# PCB-BI8-2x4C3.net
KiCad netlist of a schematic drawn in EAGLE
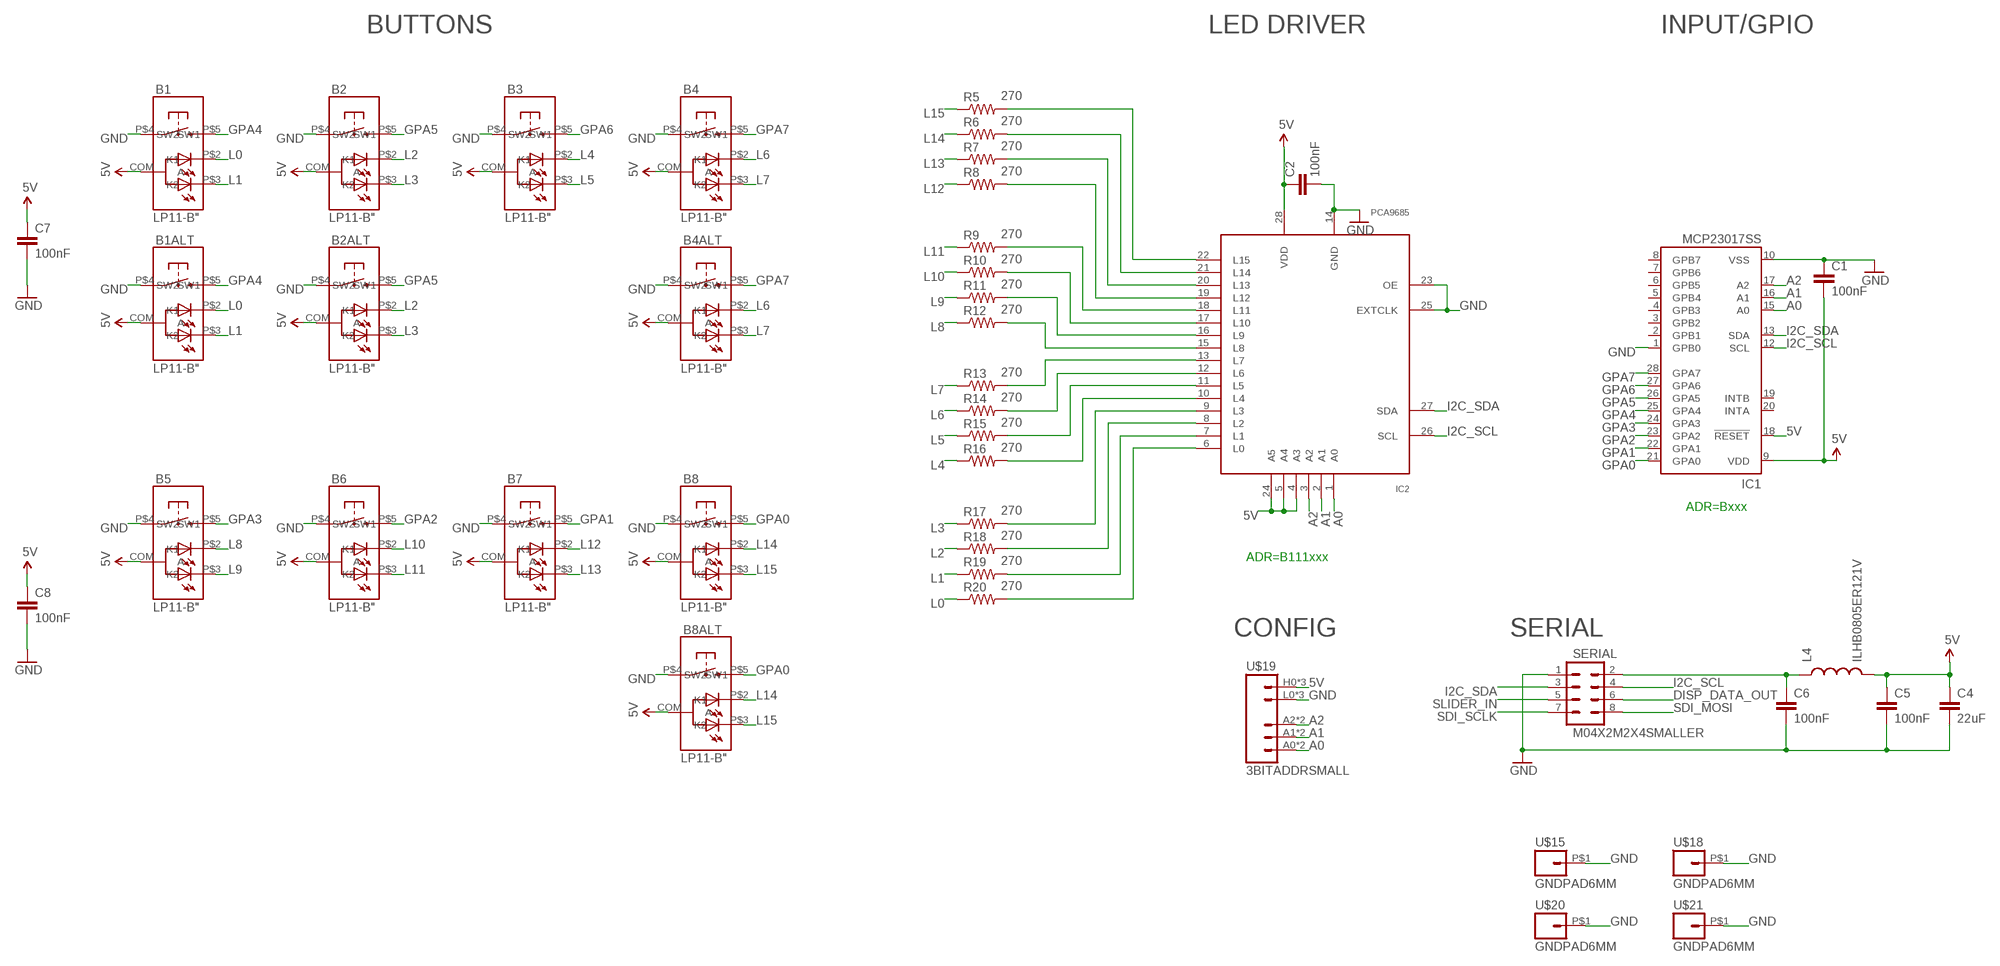
[diagram p0: schematic, sheet 1]

(export (version "E")
  (design (tool "Eeschema 10.0.6"))
  (components
    (comp (ref "B1")
      (value "LP11-B\"")
      (footprint "eagle-import:LP11")
      (libsource (lib "eagle-import") (part "LP11-B{dblquote}"))
    )
    (comp (ref "B1ALT")
      (value "LP11-B\"")
      (footprint "eagle-import:LP11")
      (libsource (lib "eagle-import") (part "LP11-B{dblquote}"))
    )
    (comp (ref "B2")
      (value "LP11-B\"")
      (footprint "eagle-import:LP11")
      (libsource (lib "eagle-import") (part "LP11-B{dblquote}"))
    )
    (comp (ref "B2ALT")
      (value "LP11-B\"")
      (footprint "eagle-import:LP11")
      (libsource (lib "eagle-import") (part "LP11-B{dblquote}"))
    )
    (comp (ref "B3")
      (value "LP11-B\"")
      (footprint "eagle-import:LP11")
      (libsource (lib "eagle-import") (part "LP11-B{dblquote}"))
    )
    (comp (ref "B4")
      (value "LP11-B\"")
      (footprint "eagle-import:LP11")
      (libsource (lib "eagle-import") (part "LP11-B{dblquote}"))
    )
    (comp (ref "B4ALT")
      (value "LP11-B\"")
      (footprint "eagle-import:LP11")
      (libsource (lib "eagle-import") (part "LP11-B{dblquote}"))
    )
    (comp (ref "B5")
      (value "LP11-B\"")
      (footprint "eagle-import:LP11")
      (libsource (lib "eagle-import") (part "LP11-B{dblquote}"))
    )
    (comp (ref "B6")
      (value "LP11-B\"")
      (footprint "eagle-import:LP11")
      (libsource (lib "eagle-import") (part "LP11-B{dblquote}"))
    )
    (comp (ref "B7")
      (value "LP11-B\"")
      (footprint "eagle-import:LP11")
      (libsource (lib "eagle-import") (part "LP11-B{dblquote}"))
    )
    (comp (ref "B8")
      (value "LP11-B\"")
      (footprint "eagle-import:LP11")
      (libsource (lib "eagle-import") (part "LP11-B{dblquote}"))
    )
    (comp (ref "B8ALT")
      (value "LP11-B\"")
      (footprint "eagle-import:LP11")
      (libsource (lib "eagle-import") (part "LP11-B{dblquote}"))
    )
    (comp (ref "C1")
      (value "100nF")
      (footprint "eagle-import:0603-CAP")
      (libsource (lib "eagle-import") (part "CAP0603-CAP"))
    )
    (comp (ref "C2")
      (value "100nF")
      (footprint "eagle-import:0603-CAP")
      (libsource (lib "eagle-import") (part "CAP0603-CAP"))
    )
    (comp (ref "C4")
      (value "22uF")
      (footprint "eagle-import:0805")
      (libsource (lib "eagle-import") (part "CAP0805"))
    )
    (comp (ref "C5")
      (value "100nF")
      (footprint "eagle-import:0603-CAP")
      (libsource (lib "eagle-import") (part "CAP0603-CAP"))
    )
    (comp (ref "C6")
      (value "100nF")
      (footprint "eagle-import:0603-CAP")
      (libsource (lib "eagle-import") (part "CAP0603-CAP"))
    )
    (comp (ref "C7")
      (value "100nF")
      (footprint "eagle-import:0603-CAP")
      (libsource (lib "eagle-import") (part "CAP0603-CAP"))
    )
    (comp (ref "C8")
      (value "100nF")
      (footprint "eagle-import:0603-CAP")
      (libsource (lib "eagle-import") (part "CAP0603-CAP"))
    )
    (comp (ref "IC1")
      (value "MCP23017SS")
      (footprint "eagle-import:SSOP28")
      (fields
        (field (name "MF") "MICROCHIP")
        (field (name "MPN") "MCP23017-E/SS")
        (field (name "MPN_1") "MCP23017-E/SS")
        (field (name "OC_FARNELL") "1467674")
        (field (name "OC_NEWARK") "31K2960")
      )
      (libsource (lib "eagle-import") (part "MCP23017SS"))
    )
    (comp (ref "IC2")
      (value "PCA9685")
      (footprint "eagle-import:TSSOP28")
      (libsource (lib "eagle-import") (part "PCA9685"))
    )
    (comp (ref "L4")
      (value "ILHB0805ER121V")
      (footprint "eagle-import:0805")
      (libsource (lib "eagle-import") (part "INDUCTOR0805"))
    )
    (comp (ref "R5")
      (value "270")
      (footprint "eagle-import:0603-RES")
      (libsource (lib "eagle-import") (part "RESISTOR0603-RES"))
    )
    (comp (ref "R6")
      (value "270")
      (footprint "eagle-import:0603-RES")
      (libsource (lib "eagle-import") (part "RESISTOR0603-RES"))
    )
    (comp (ref "R7")
      (value "270")
      (footprint "eagle-import:0603-RES")
      (libsource (lib "eagle-import") (part "RESISTOR0603-RES"))
    )
    (comp (ref "R8")
      (value "270")
      (footprint "eagle-import:0603-RES")
      (libsource (lib "eagle-import") (part "RESISTOR0603-RES"))
    )
    (comp (ref "R9")
      (value "270")
      (footprint "eagle-import:0603-RES")
      (libsource (lib "eagle-import") (part "RESISTOR0603-RES"))
    )
    (comp (ref "R10")
      (value "270")
      (footprint "eagle-import:0603-RES")
      (libsource (lib "eagle-import") (part "RESISTOR0603-RES"))
    )
    (comp (ref "R11")
      (value "270")
      (footprint "eagle-import:0603-RES")
      (libsource (lib "eagle-import") (part "RESISTOR0603-RES"))
    )
    (comp (ref "R12")
      (value "270")
      (footprint "eagle-import:0603-RES")
      (libsource (lib "eagle-import") (part "RESISTOR0603-RES"))
    )
    (comp (ref "R13")
      (value "270")
      (footprint "eagle-import:0603-RES")
      (libsource (lib "eagle-import") (part "RESISTOR0603-RES"))
    )
    (comp (ref "R14")
      (value "270")
      (footprint "eagle-import:0603-RES")
      (libsource (lib "eagle-import") (part "RESISTOR0603-RES"))
    )
    (comp (ref "R15")
      (value "270")
      (footprint "eagle-import:0603-RES")
      (libsource (lib "eagle-import") (part "RESISTOR0603-RES"))
    )
    (comp (ref "R16")
      (value "270")
      (footprint "eagle-import:0603-RES")
      (libsource (lib "eagle-import") (part "RESISTOR0603-RES"))
    )
    (comp (ref "R17")
      (value "270")
      (footprint "eagle-import:0603-RES")
      (libsource (lib "eagle-import") (part "RESISTOR0603-RES"))
    )
    (comp (ref "R18")
      (value "270")
      (footprint "eagle-import:0603-RES")
      (libsource (lib "eagle-import") (part "RESISTOR0603-RES"))
    )
    (comp (ref "R19")
      (value "270")
      (footprint "eagle-import:0603-RES")
      (libsource (lib "eagle-import") (part "RESISTOR0603-RES"))
    )
    (comp (ref "R20")
      (value "270")
      (footprint "eagle-import:0603-RES")
      (libsource (lib "eagle-import") (part "RESISTOR0603-RES"))
    )
    (comp (ref "SERIAL")
      (value "M04X2M2X4SMALLER")
      (footprint "eagle-import:M2X4SMALLER")
      (libsource (lib "eagle-import") (part "M04X2M2X4SMALLER"))
    )
    (comp (ref "U$15")
      (value "GNDPAD6MM")
      (footprint "eagle-import:3.2MMPAD6MM")
      (libsource (lib "eagle-import") (part "GNDPAD6MM"))
    )
    (comp (ref "U$18")
      (value "GNDPAD6MM")
      (footprint "eagle-import:3.2MMPAD6MM")
      (libsource (lib "eagle-import") (part "GNDPAD6MM"))
    )
    (comp (ref "U$19")
      (value "3BITADDRSMALL")
      (footprint "eagle-import:3BITADDR_SMALL")
      (libsource (lib "eagle-import") (part "3BITADDRSMALL"))
    )
    (comp (ref "U$20")
      (value "GNDPAD6MM")
      (footprint "eagle-import:3.2MMPAD6MM")
      (libsource (lib "eagle-import") (part "GNDPAD6MM"))
    )
    (comp (ref "U$21")
      (value "GNDPAD6MM")
      (footprint "eagle-import:3.2MMPAD6MM")
      (libsource (lib "eagle-import") (part "GNDPAD6MM"))
    )
  )
  (nets
    (net (code "1") (name "5V") (class "Default")
      (node (ref "B1") (pin "COM") (pinfunction "A_COM") (pintype "bidirectional"))
      (node (ref "B1ALT") (pin "COM") (pinfunction "A_COM") (pintype "bidirectional"))
      (node (ref "B2") (pin "COM") (pinfunction "A_COM") (pintype "bidirectional"))
      (node (ref "B2ALT") (pin "COM") (pinfunction "A_COM") (pintype "bidirectional"))
      (node (ref "B3") (pin "COM") (pinfunction "A_COM") (pintype "bidirectional"))
      (node (ref "B4") (pin "COM") (pinfunction "A_COM") (pintype "bidirectional"))
      (node (ref "B4ALT") (pin "COM") (pinfunction "A_COM") (pintype "bidirectional"))
      (node (ref "B5") (pin "COM") (pinfunction "A_COM") (pintype "bidirectional"))
      (node (ref "B6") (pin "COM") (pinfunction "A_COM") (pintype "bidirectional"))
      (node (ref "B7") (pin "COM") (pinfunction "A_COM") (pintype "bidirectional"))
      (node (ref "B8") (pin "COM") (pinfunction "A_COM") (pintype "bidirectional"))
      (node (ref "B8ALT") (pin "COM") (pinfunction "A_COM") (pintype "bidirectional"))
      (node (ref "C1") (pin "2") (pinfunction "2_2") (pintype "passive"))
      (node (ref "C2") (pin "1") (pinfunction "1_1") (pintype "passive"))
      (node (ref "C4") (pin "1") (pinfunction "1_1") (pintype "passive"))
      (node (ref "C5") (pin "1") (pinfunction "1_1") (pintype "passive"))
      (node (ref "C7") (pin "1") (pinfunction "1_1") (pintype "passive"))
      (node (ref "C8") (pin "1") (pinfunction "1_1") (pintype "passive"))
      (node (ref "IC1") (pin "18") (pinfunction "~{RESET}_18") (pintype "input"))
      (node (ref "IC1") (pin "9") (pinfunction "VDD_9") (pintype "power_in"))
      (node (ref "IC2") (pin "24") (pinfunction "A5_24") (pintype "input"))
      (node (ref "IC2") (pin "28") (pinfunction "VDD_28") (pintype "power_in"))
      (node (ref "IC2") (pin "4") (pinfunction "A3_4") (pintype "input"))
      (node (ref "IC2") (pin "5") (pinfunction "A4_5") (pintype "input"))
      (node (ref "L4") (pin "2") (pinfunction "2_2") (pintype "passive"))
      (node (ref "U$19") (pin "H0") (pinfunction "VCC_H0") (pintype "passive"))
      (node (ref "U$19") (pin "H1") (pinfunction "VCC_H1") (pintype "passive"))
      (node (ref "U$19") (pin "H2") (pinfunction "VCC_H2") (pintype "passive"))
    )
    (net (code "2") (name "A0") (class "Default")
      (node (ref "IC1") (pin "15") (pinfunction "A0_15") (pintype "input"))
      (node (ref "IC2") (pin "1") (pinfunction "A0_1") (pintype "input"))
      (node (ref "U$19") (pin "A0") (pinfunction "A0_A0") (pintype "passive"))
      (node (ref "U$19") (pin "AS0") (pinfunction "A0_AS0") (pintype "passive"))
    )
    (net (code "3") (name "A1") (class "Default")
      (node (ref "IC1") (pin "16") (pinfunction "A1_16") (pintype "input"))
      (node (ref "IC2") (pin "2") (pinfunction "A1_2") (pintype "input"))
      (node (ref "U$19") (pin "A1") (pinfunction "A1_A1") (pintype "passive"))
      (node (ref "U$19") (pin "AS1") (pinfunction "A1_AS1") (pintype "passive"))
    )
    (net (code "4") (name "A2") (class "Default")
      (node (ref "IC1") (pin "17") (pinfunction "A2_17") (pintype "input"))
      (node (ref "IC2") (pin "3") (pinfunction "A2_3") (pintype "input"))
      (node (ref "U$19") (pin "A2") (pinfunction "A2_A2") (pintype "passive"))
      (node (ref "U$19") (pin "AS2") (pinfunction "A2_AS2") (pintype "passive"))
    )
    (net (code "5") (name "DISP_DATA_OUT") (class "Default")
      (node (ref "SERIAL") (pin "6") (pinfunction "6_6") (pintype "passive"))
    )
    (net (code "6") (name "GND") (class "Default")
      (node (ref "B1") (pin "P$4") (pinfunction "SW1_P$4") (pintype "bidirectional"))
      (node (ref "B1ALT") (pin "P$4") (pinfunction "SW1_P$4") (pintype "bidirectional"))
      (node (ref "B2") (pin "P$4") (pinfunction "SW1_P$4") (pintype "bidirectional"))
      (node (ref "B2ALT") (pin "P$4") (pinfunction "SW1_P$4") (pintype "bidirectional"))
      (node (ref "B3") (pin "P$4") (pinfunction "SW1_P$4") (pintype "bidirectional"))
      (node (ref "B4") (pin "P$4") (pinfunction "SW1_P$4") (pintype "bidirectional"))
      (node (ref "B4ALT") (pin "P$4") (pinfunction "SW1_P$4") (pintype "bidirectional"))
      (node (ref "B5") (pin "P$4") (pinfunction "SW1_P$4") (pintype "bidirectional"))
      (node (ref "B6") (pin "P$4") (pinfunction "SW1_P$4") (pintype "bidirectional"))
      (node (ref "B7") (pin "P$4") (pinfunction "SW1_P$4") (pintype "bidirectional"))
      (node (ref "B8") (pin "P$4") (pinfunction "SW1_P$4") (pintype "bidirectional"))
      (node (ref "B8ALT") (pin "P$4") (pinfunction "SW1_P$4") (pintype "bidirectional"))
      (node (ref "C1") (pin "1") (pinfunction "1_1") (pintype "passive"))
      (node (ref "C2") (pin "2") (pinfunction "2_2") (pintype "passive"))
      (node (ref "C4") (pin "2") (pinfunction "2_2") (pintype "passive"))
      (node (ref "C5") (pin "2") (pinfunction "2_2") (pintype "passive"))
      (node (ref "C6") (pin "2") (pinfunction "2_2") (pintype "passive"))
      (node (ref "C7") (pin "2") (pinfunction "2_2") (pintype "passive"))
      (node (ref "C8") (pin "2") (pinfunction "2_2") (pintype "passive"))
      (node (ref "IC1") (pin "1") (pinfunction "GPB0_1") (pintype "bidirectional"))
      (node (ref "IC1") (pin "10") (pinfunction "VSS_10") (pintype "power_in"))
      (node (ref "IC2") (pin "14") (pinfunction "GND_14") (pintype "power_in"))
      (node (ref "IC2") (pin "23") (pinfunction "OE_23") (pintype "input"))
      (node (ref "IC2") (pin "25") (pinfunction "EXTCLK_25") (pintype "input"))
      (node (ref "SERIAL") (pin "1") (pinfunction "1_1") (pintype "passive"))
      (node (ref "U$15") (pin "P$1") (pinfunction "1_P$1") (pintype "passive"))
      (node (ref "U$18") (pin "P$1") (pinfunction "1_P$1") (pintype "passive"))
      (node (ref "U$19") (pin "L0") (pinfunction "GND_L0") (pintype "passive"))
      (node (ref "U$19") (pin "L1") (pinfunction "GND_L1") (pintype "passive"))
      (node (ref "U$19") (pin "L2") (pinfunction "GND_L2") (pintype "passive"))
      (node (ref "U$20") (pin "P$1") (pinfunction "1_P$1") (pintype "passive"))
      (node (ref "U$21") (pin "P$1") (pinfunction "1_P$1") (pintype "passive"))
    )
    (net (code "7") (name "GPA0") (class "Default")
      (node (ref "B8") (pin "P$5") (pinfunction "SW2_P$5") (pintype "bidirectional"))
      (node (ref "B8ALT") (pin "P$5") (pinfunction "SW2_P$5") (pintype "bidirectional"))
      (node (ref "IC1") (pin "21") (pinfunction "GPA0_21") (pintype "bidirectional"))
    )
    (net (code "8") (name "GPA1") (class "Default")
      (node (ref "B7") (pin "P$5") (pinfunction "SW2_P$5") (pintype "bidirectional"))
      (node (ref "IC1") (pin "22") (pinfunction "GPA1_22") (pintype "bidirectional"))
    )
    (net (code "9") (name "GPA2") (class "Default")
      (node (ref "B6") (pin "P$5") (pinfunction "SW2_P$5") (pintype "bidirectional"))
      (node (ref "IC1") (pin "23") (pinfunction "GPA2_23") (pintype "bidirectional"))
    )
    (net (code "10") (name "GPA3") (class "Default")
      (node (ref "B5") (pin "P$5") (pinfunction "SW2_P$5") (pintype "bidirectional"))
      (node (ref "IC1") (pin "24") (pinfunction "GPA3_24") (pintype "bidirectional"))
    )
    (net (code "11") (name "GPA4") (class "Default")
      (node (ref "B1") (pin "P$5") (pinfunction "SW2_P$5") (pintype "bidirectional"))
      (node (ref "B1ALT") (pin "P$5") (pinfunction "SW2_P$5") (pintype "bidirectional"))
      (node (ref "IC1") (pin "25") (pinfunction "GPA4_25") (pintype "bidirectional"))
    )
    (net (code "12") (name "GPA5") (class "Default")
      (node (ref "B2") (pin "P$5") (pinfunction "SW2_P$5") (pintype "bidirectional"))
      (node (ref "B2ALT") (pin "P$5") (pinfunction "SW2_P$5") (pintype "bidirectional"))
      (node (ref "IC1") (pin "26") (pinfunction "GPA5_26") (pintype "bidirectional"))
    )
    (net (code "13") (name "GPA6") (class "Default")
      (node (ref "B3") (pin "P$5") (pinfunction "SW2_P$5") (pintype "bidirectional"))
      (node (ref "IC1") (pin "27") (pinfunction "GPA6_27") (pintype "bidirectional"))
    )
    (net (code "14") (name "GPA7") (class "Default")
      (node (ref "B4") (pin "P$5") (pinfunction "SW2_P$5") (pintype "bidirectional"))
      (node (ref "B4ALT") (pin "P$5") (pinfunction "SW2_P$5") (pintype "bidirectional"))
      (node (ref "IC1") (pin "28") (pinfunction "GPA7_28") (pintype "bidirectional"))
    )
    (net (code "15") (name "I2C_SCL") (class "Default")
      (node (ref "IC1") (pin "12") (pinfunction "SCL_12") (pintype "input"))
      (node (ref "IC2") (pin "26") (pinfunction "SCL_26") (pintype "input"))
      (node (ref "SERIAL") (pin "4") (pinfunction "4_4") (pintype "passive"))
    )
    (net (code "16") (name "I2C_SDA") (class "Default")
      (node (ref "IC1") (pin "13") (pinfunction "SDA_13") (pintype "bidirectional"))
      (node (ref "IC2") (pin "27") (pinfunction "SDA_27") (pintype "input"))
      (node (ref "SERIAL") (pin "3") (pinfunction "3_3") (pintype "passive"))
    )
    (net (code "17") (name "L0") (class "Default")
      (node (ref "B1") (pin "P$2") (pinfunction "K1_P$2") (pintype "bidirectional"))
      (node (ref "B1ALT") (pin "P$2") (pinfunction "K1_P$2") (pintype "bidirectional"))
      (node (ref "R20") (pin "1") (pinfunction "1_1") (pintype "passive"))
    )
    (net (code "18") (name "L1") (class "Default")
      (node (ref "B1") (pin "P$3") (pinfunction "K2_P$3") (pintype "bidirectional"))
      (node (ref "B1ALT") (pin "P$3") (pinfunction "K2_P$3") (pintype "bidirectional"))
      (node (ref "R19") (pin "1") (pinfunction "1_1") (pintype "passive"))
    )
    (net (code "19") (name "L2") (class "Default")
      (node (ref "B2") (pin "P$2") (pinfunction "K1_P$2") (pintype "bidirectional"))
      (node (ref "B2ALT") (pin "P$2") (pinfunction "K1_P$2") (pintype "bidirectional"))
      (node (ref "R18") (pin "1") (pinfunction "1_1") (pintype "passive"))
    )
    (net (code "20") (name "L3") (class "Default")
      (node (ref "B2") (pin "P$3") (pinfunction "K2_P$3") (pintype "bidirectional"))
      (node (ref "B2ALT") (pin "P$3") (pinfunction "K2_P$3") (pintype "bidirectional"))
      (node (ref "R17") (pin "1") (pinfunction "1_1") (pintype "passive"))
    )
    (net (code "21") (name "L4") (class "Default")
      (node (ref "B3") (pin "P$2") (pinfunction "K1_P$2") (pintype "bidirectional"))
      (node (ref "R16") (pin "1") (pinfunction "1_1") (pintype "passive"))
    )
    (net (code "22") (name "L5") (class "Default")
      (node (ref "B3") (pin "P$3") (pinfunction "K2_P$3") (pintype "bidirectional"))
      (node (ref "R15") (pin "1") (pinfunction "1_1") (pintype "passive"))
    )
    (net (code "23") (name "L6") (class "Default")
      (node (ref "B4") (pin "P$2") (pinfunction "K1_P$2") (pintype "bidirectional"))
      (node (ref "B4ALT") (pin "P$2") (pinfunction "K1_P$2") (pintype "bidirectional"))
      (node (ref "R14") (pin "1") (pinfunction "1_1") (pintype "passive"))
    )
    (net (code "24") (name "L7") (class "Default")
      (node (ref "B4") (pin "P$3") (pinfunction "K2_P$3") (pintype "bidirectional"))
      (node (ref "B4ALT") (pin "P$3") (pinfunction "K2_P$3") (pintype "bidirectional"))
      (node (ref "R13") (pin "1") (pinfunction "1_1") (pintype "passive"))
    )
    (net (code "25") (name "L8") (class "Default")
      (node (ref "B5") (pin "P$2") (pinfunction "K1_P$2") (pintype "bidirectional"))
      (node (ref "R12") (pin "1") (pinfunction "1_1") (pintype "passive"))
    )
    (net (code "26") (name "L9") (class "Default")
      (node (ref "B5") (pin "P$3") (pinfunction "K2_P$3") (pintype "bidirectional"))
      (node (ref "R11") (pin "1") (pinfunction "1_1") (pintype "passive"))
    )
    (net (code "27") (name "L10") (class "Default")
      (node (ref "B6") (pin "P$2") (pinfunction "K1_P$2") (pintype "bidirectional"))
      (node (ref "R10") (pin "1") (pinfunction "1_1") (pintype "passive"))
    )
    (net (code "28") (name "L11") (class "Default")
      (node (ref "B6") (pin "P$3") (pinfunction "K2_P$3") (pintype "bidirectional"))
      (node (ref "R9") (pin "1") (pinfunction "1_1") (pintype "passive"))
    )
    (net (code "29") (name "L12") (class "Default")
      (node (ref "B7") (pin "P$2") (pinfunction "K1_P$2") (pintype "bidirectional"))
      (node (ref "R8") (pin "1") (pinfunction "1_1") (pintype "passive"))
    )
    (net (code "30") (name "L13") (class "Default")
      (node (ref "B7") (pin "P$3") (pinfunction "K2_P$3") (pintype "bidirectional"))
      (node (ref "R7") (pin "1") (pinfunction "1_1") (pintype "passive"))
    )
    (net (code "31") (name "L14") (class "Default")
      (node (ref "B8") (pin "P$2") (pinfunction "K1_P$2") (pintype "bidirectional"))
      (node (ref "B8ALT") (pin "P$2") (pinfunction "K1_P$2") (pintype "bidirectional"))
      (node (ref "R6") (pin "1") (pinfunction "1_1") (pintype "passive"))
    )
    (net (code "32") (name "L15") (class "Default")
      (node (ref "B8") (pin "P$3") (pinfunction "K2_P$3") (pintype "bidirectional"))
      (node (ref "B8ALT") (pin "P$3") (pinfunction "K2_P$3") (pintype "bidirectional"))
      (node (ref "R5") (pin "1") (pinfunction "1_1") (pintype "passive"))
    )
    (net (code "33") (name "Net-(C6-Pad1)") (class "Default")
      (node (ref "C6") (pin "1") (pinfunction "1_1") (pintype "passive"))
      (node (ref "L4") (pin "1") (pinfunction "1_1") (pintype "passive"))
      (node (ref "SERIAL") (pin "2") (pinfunction "2_2") (pintype "passive"))
    )
    (net (code "34") (name "Net-(IC2-L0)") (class "Default")
      (node (ref "IC2") (pin "6") (pinfunction "L0_6") (pintype "output"))
      (node (ref "R20") (pin "2") (pinfunction "2_2") (pintype "passive"))
    )
    (net (code "35") (name "Net-(IC2-L1)") (class "Default")
      (node (ref "IC2") (pin "7") (pinfunction "L1_7") (pintype "output"))
      (node (ref "R19") (pin "2") (pinfunction "2_2") (pintype "passive"))
    )
    (net (code "36") (name "Net-(IC2-L2)") (class "Default")
      (node (ref "IC2") (pin "8") (pinfunction "L2_8") (pintype "output"))
      (node (ref "R18") (pin "2") (pinfunction "2_2") (pintype "passive"))
    )
    (net (code "37") (name "Net-(IC2-L3)") (class "Default")
      (node (ref "IC2") (pin "9") (pinfunction "L3_9") (pintype "output"))
      (node (ref "R17") (pin "2") (pinfunction "2_2") (pintype "passive"))
    )
    (net (code "38") (name "Net-(IC2-L4)") (class "Default")
      (node (ref "IC2") (pin "10") (pinfunction "L4_10") (pintype "output"))
      (node (ref "R16") (pin "2") (pinfunction "2_2") (pintype "passive"))
    )
    (net (code "39") (name "Net-(IC2-L5)") (class "Default")
      (node (ref "IC2") (pin "11") (pinfunction "L5_11") (pintype "output"))
      (node (ref "R15") (pin "2") (pinfunction "2_2") (pintype "passive"))
    )
    (net (code "40") (name "Net-(IC2-L6)") (class "Default")
      (node (ref "IC2") (pin "12") (pinfunction "L6_12") (pintype "output"))
      (node (ref "R14") (pin "2") (pinfunction "2_2") (pintype "passive"))
    )
    (net (code "41") (name "Net-(IC2-L7)") (class "Default")
      (node (ref "IC2") (pin "13") (pinfunction "L7_13") (pintype "output"))
      (node (ref "R13") (pin "2") (pinfunction "2_2") (pintype "passive"))
    )
    (net (code "42") (name "Net-(IC2-L8)") (class "Default")
      (node (ref "IC2") (pin "15") (pinfunction "L8_15") (pintype "output"))
      (node (ref "R12") (pin "2") (pinfunction "2_2") (pintype "passive"))
    )
    (net (code "43") (name "Net-(IC2-L9)") (class "Default")
      (node (ref "IC2") (pin "16") (pinfunction "L9_16") (pintype "output"))
      (node (ref "R11") (pin "2") (pinfunction "2_2") (pintype "passive"))
    )
    (net (code "44") (name "Net-(IC2-L10)") (class "Default")
      (node (ref "IC2") (pin "17") (pinfunction "L10_17") (pintype "output"))
      (node (ref "R10") (pin "2") (pinfunction "2_2") (pintype "passive"))
    )
    (net (code "45") (name "Net-(IC2-L11)") (class "Default")
      (node (ref "IC2") (pin "18") (pinfunction "L11_18") (pintype "output"))
      (node (ref "R9") (pin "2") (pinfunction "2_2") (pintype "passive"))
    )
    (net (code "46") (name "Net-(IC2-L12)") (class "Default")
      (node (ref "IC2") (pin "19") (pinfunction "L12_19") (pintype "output"))
      (node (ref "R8") (pin "2") (pinfunction "2_2") (pintype "passive"))
    )
    (net (code "47") (name "Net-(IC2-L13)") (class "Default")
      (node (ref "IC2") (pin "20") (pinfunction "L13_20") (pintype "output"))
      (node (ref "R7") (pin "2") (pinfunction "2_2") (pintype "passive"))
    )
    (net (code "48") (name "Net-(IC2-L14)") (class "Default")
      (node (ref "IC2") (pin "21") (pinfunction "L14_21") (pintype "output"))
      (node (ref "R6") (pin "2") (pinfunction "2_2") (pintype "passive"))
    )
    (net (code "49") (name "Net-(IC2-L15)") (class "Default")
      (node (ref "IC2") (pin "22") (pinfunction "L15_22") (pintype "output"))
      (node (ref "R5") (pin "2") (pinfunction "2_2") (pintype "passive"))
    )
    (net (code "50") (name "SDI_MOSI") (class "Default")
      (node (ref "SERIAL") (pin "8") (pinfunction "8_8") (pintype "passive"))
    )
    (net (code "51") (name "SDI_SCLK") (class "Default")
      (node (ref "SERIAL") (pin "7") (pinfunction "7_7") (pintype "passive"))
    )
    (net (code "52") (name "SLIDER_IN") (class "Default")
      (node (ref "SERIAL") (pin "5") (pinfunction "5_5") (pintype "passive"))
    )
    (net (code "53") (name "unconnected-(IC1-GPB1-Pad2)") (class "Default")
      (node (ref "IC1") (pin "2") (pinfunction "GPB1_2") (pintype "bidirectional"))
    )
    (net (code "54") (name "unconnected-(IC1-GPB2-Pad3)") (class "Default")
      (node (ref "IC1") (pin "3") (pinfunction "GPB2_3") (pintype "bidirectional"))
    )
    (net (code "55") (name "unconnected-(IC1-GPB3-Pad4)") (class "Default")
      (node (ref "IC1") (pin "4") (pinfunction "GPB3_4") (pintype "bidirectional"))
    )
    (net (code "56") (name "unconnected-(IC1-GPB4-Pad5)") (class "Default")
      (node (ref "IC1") (pin "5") (pinfunction "GPB4_5") (pintype "bidirectional"))
    )
    (net (code "57") (name "unconnected-(IC1-GPB5-Pad6)") (class "Default")
      (node (ref "IC1") (pin "6") (pinfunction "GPB5_6") (pintype "bidirectional"))
    )
    (net (code "58") (name "unconnected-(IC1-GPB6-Pad7)") (class "Default")
      (node (ref "IC1") (pin "7") (pinfunction "GPB6_7") (pintype "bidirectional"))
    )
    (net (code "59") (name "unconnected-(IC1-GPB7-Pad8)") (class "Default")
      (node (ref "IC1") (pin "8") (pinfunction "GPB7_8") (pintype "bidirectional"))
    )
    (net (code "60") (name "unconnected-(IC1-INTA-Pad20)") (class "Default")
      (node (ref "IC1") (pin "20") (pinfunction "INTA_20") (pintype "output"))
    )
    (net (code "61") (name "unconnected-(IC1-INTB-Pad19)") (class "Default")
      (node (ref "IC1") (pin "19") (pinfunction "INTB_19") (pintype "output"))
    )
  )
)
